# hv_mux_tr_sw.net
KiCad netlist of a schematic drawn in Altium Designer
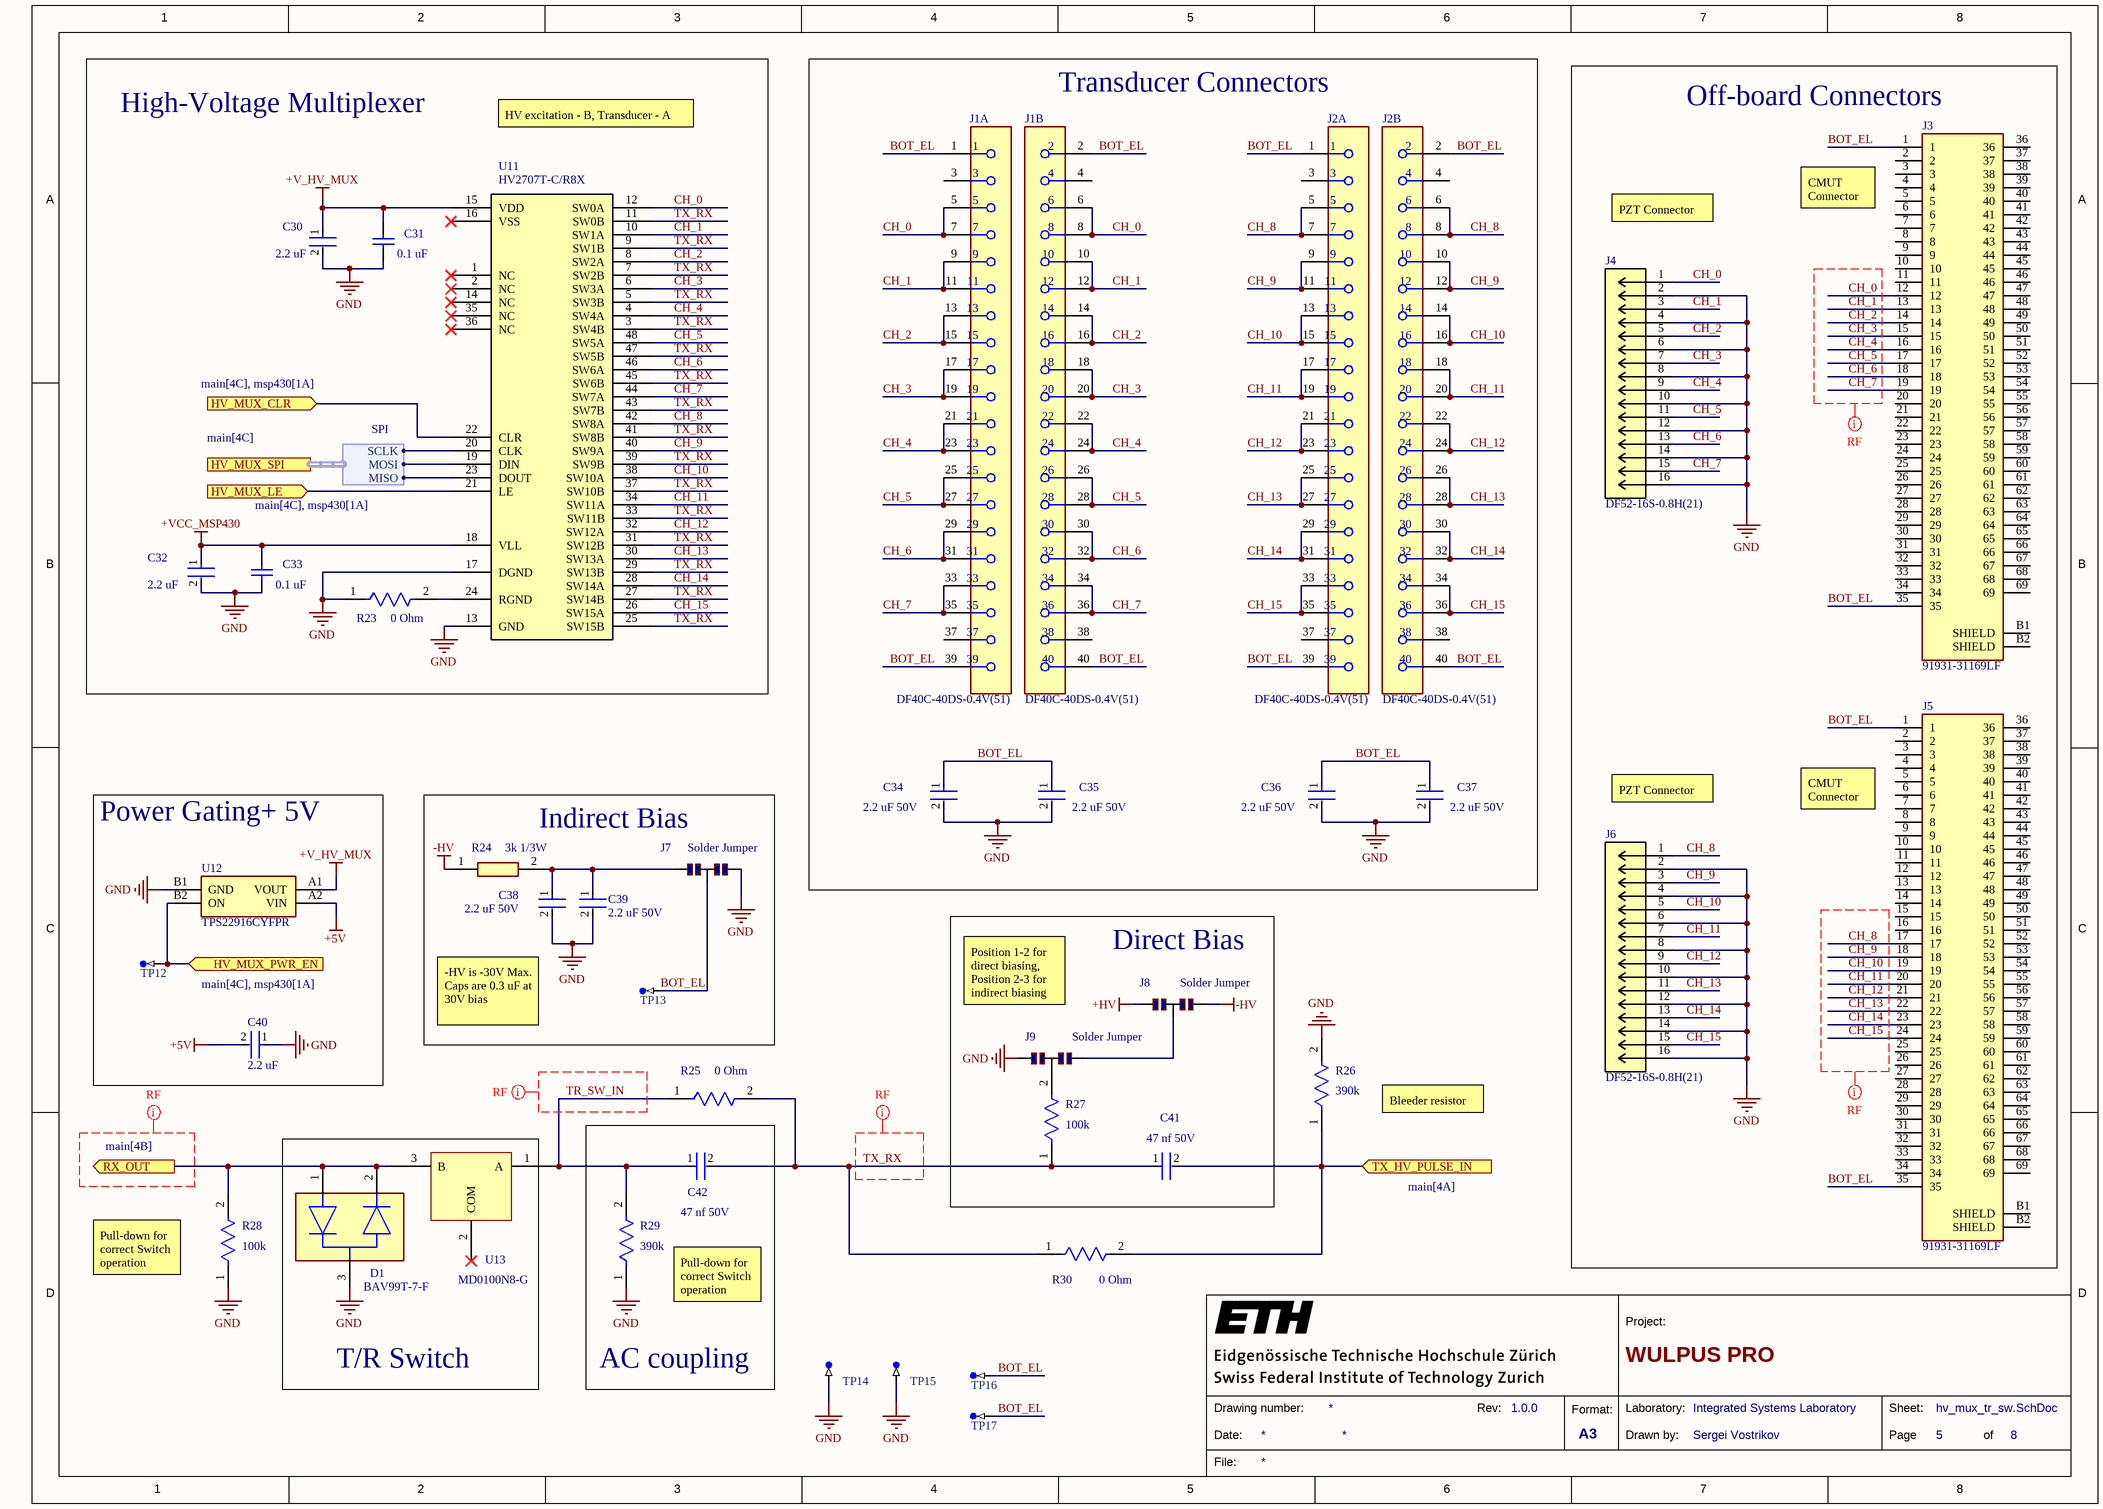
[diagram p0: hv_mux_tr_sw.SchDoc]

(export (version "E")
  (design (tool "Eeschema 10.0.6"))
  (components
    (comp (ref "C30")
      (value "2.2 uF")
      (footprint "FP-C1005-050-0_15-0_1-MFG")
      (description "C1005X7S1A225K050BC")
      (fields (field (name "TOLERANCE") "10%"))
      (libsource (lib "Altium Content Vault") (part "b4654b650e69147ec39a6b967a45e02"))
    )
    (comp (ref "C31")
      (value "0.1 uF")
      (footprint "CAPC1005X55X30LL05T10")
      (description "C0402C104K4RACTU")
      (fields (field (name "MANUFACTURER") "Kemet"))
      (libsource (lib "Altium Content Vault") (part "CAP"))
    )
    (comp (ref "C32")
      (value "2.2 uF")
      (footprint "FP-C1005-050-0_15-0_1-MFG")
      (description "C1005X7S1A225K050BC")
      (fields (field (name "TOLERANCE") "10%"))
      (libsource (lib "Altium Content Vault") (part "b4654b650e69147ec39a6b967a45e02"))
    )
    (comp (ref "C33")
      (value "0.1 uF")
      (footprint "CAPC1005X55X30LL05T10")
      (description "C0402C104K4RACTU")
      (fields (field (name "MANUFACTURER") "Kemet"))
      (libsource (lib "Altium Content Vault") (part "CAP"))
    )
    (comp (ref "C34")
      (value "2.2 uF 50V")
      (footprint "FP-GRM188-0_2-IPC_B")
      (description "GRM188R61H225ME11")
      (fields (field (name "TOLERANCE") "20%"))
      (libsource (lib "Altium Content Vault") (part "11868f565c42a9108669ba33697ecf6"))
    )
    (comp (ref "C35")
      (value "2.2 uF 50V")
      (footprint "FP-GRM188-0_2-IPC_B")
      (description "GRM188R61H225ME11")
      (fields (field (name "TOLERANCE") "20%"))
      (libsource (lib "Altium Content Vault") (part "11868f565c42a9108669ba33697ecf6"))
    )
    (comp (ref "C36")
      (value "2.2 uF 50V")
      (footprint "FP-GRM188-0_2-IPC_B")
      (description "GRM188R61H225ME11")
      (fields (field (name "TOLERANCE") "20%"))
      (libsource (lib "Altium Content Vault") (part "11868f565c42a9108669ba33697ecf6"))
    )
    (comp (ref "C37")
      (value "2.2 uF 50V")
      (footprint "FP-GRM188-0_2-IPC_B")
      (description "GRM188R61H225ME11")
      (fields (field (name "TOLERANCE") "20%"))
      (libsource (lib "Altium Content Vault") (part "11868f565c42a9108669ba33697ecf6"))
    )
    (comp (ref "C38")
      (value "2.2 uF 50V")
      (footprint "FP-GRM188-0_2-IPC_B")
      (description "GRM188R61H225ME11")
      (fields (field (name "TOLERANCE") "20%"))
      (libsource (lib "Altium Content Vault") (part "11868f565c42a9108669ba33697ecf6"))
    )
    (comp (ref "C39")
      (value "2.2 uF 50V")
      (footprint "FP-GRM188-0_2-IPC_B")
      (description "GRM188R61H225ME11")
      (fields (field (name "TOLERANCE") "20%"))
      (libsource (lib "Altium Content Vault") (part "11868f565c42a9108669ba33697ecf6"))
    )
    (comp (ref "C40")
      (value "2.2 uF")
      (footprint "FP-C1005-050-0_15-0_1-MFG")
      (description "C1005X7S1A225K050BC")
      (fields (field (name "TOLERANCE") "10%"))
      (libsource (lib "Altium Content Vault") (part "b4654b650e69147ec39a6b967a45e02"))
    )
    (comp (ref "C41")
      (value "47 nf 50V")
      (footprint "FP-GRM155-0_05-IPC_C")
      (description "GRM155R71H473ME14D")
      (fields (field (name "TOLERANCE") "20%"))
      (libsource (lib "Altium Content Vault") (part "02cd4be3c70576c341d710602a673aa"))
    )
    (comp (ref "C42")
      (value "47 nf 50V")
      (footprint "FP-GRM155-0_05-IPC_C")
      (description "GRM155R71H473ME14D")
      (fields (field (name "TOLERANCE") "20%"))
      (libsource (lib "Altium Content Vault") (part "02cd4be3c70576c341d710602a673aa"))
    )
    (comp (ref "D1")
      (value "BAV99T-7-F")
      (footprint "FP-SOT523-MFG")
      (description "DIODE ARRAY GP 85V 75MA SOT523")
      (fields
        (field (name "OCTOPART") "https://octopart.com/bav99t-7-f-diodes+inc.-326340")
        (field (name "MANUFACTURER") "Diodes Inc.")
      )
      (libsource (lib "Altium Content Vault") (part "070e4dda4d860bc04de3109e77921ad"))
    )
    (comp (ref "J1")
      (value "DF40C-40DS-0.4V(51)")
      (footprint "FP-DF40C-40DS-0_4V_51-MFG")
      (description "CONN RCPT 40POS SMD GOLD")
      (fields
        (field (name "MANUFACTURER") "Hirose")
        (field (name "OCTOPART") "https://octopart.com/df40c-40ds-0.4v%2851%29-hirose-19073526")
      )
      (libsource (lib "Altium Content Vault") (part "7acf1c4a8db21028d11741a46a6ec78"))
    )
    (comp (ref "J2")
      (value "DF40C-40DS-0.4V(51)")
      (footprint "FP-DF40C-40DS-0_4V_51-MFG")
      (description "CONN RCPT 40POS SMD GOLD")
      (fields
        (field (name "MANUFACTURER") "Hirose")
        (field (name "OCTOPART") "https://octopart.com/df40c-40ds-0.4v%2851%29-hirose-19073526")
      )
      (libsource (lib "Altium Content Vault") (part "7acf1c4a8db21028d11741a46a6ec78"))
    )
    (comp (ref "J3")
      (value "91931-31169LF")
      (footprint "cmut_conn:FRAMETOME_91931-31169LF")
      (description "Conn; Rect; Industrial; MezzanineRECP; 69Cnts; SMT; I-IndustrialSeries")
      (libsource (lib "cmut_conn") (part "91931-31169LF"))
    )
    (comp (ref "J4")
      (value "DF52-16S-0.8H(21)")
      (footprint "CONN_DF52-16S-0.8H(21)_HIR")
      (description "No Description Available")
      (fields (field (name "COPYRIGHT") "Copyright (C) 2022 Ultra Librarian. All rights reserved."))
      (libsource (lib "wulpus_hv") (part "DF52-16S-0.8H(21)"))
    )
    (comp (ref "J5")
      (value "91931-31169LF")
      (footprint "cmut_conn:FRAMETOME_91931-31169LF")
      (description "Conn; Rect; Industrial; MezzanineRECP; 69Cnts; SMT; I-IndustrialSeries")
      (libsource (lib "cmut_conn") (part "91931-31169LF"))
    )
    (comp (ref "J6")
      (value "DF52-16S-0.8H(21)")
      (footprint "CONN_DF52-16S-0.8H(21)_HIR")
      (description "No Description Available")
      (fields (field (name "COPYRIGHT") "Copyright (C) 2022 Ultra Librarian. All rights reserved."))
      (libsource (lib "wulpus_hv") (part "DF52-16S-0.8H(21)"))
    )
    (comp (ref "J7")
      (value "Solder Jumper")
      (footprint "Jumper 3 pins")
      (description "Solder Jumper 3 Pads")
      (libsource (lib "ETHZ Vault") (part "Solder Jumper 3-pads"))
    )
    (comp (ref "J8")
      (value "Solder Jumper")
      (footprint "Jumper 3 pins")
      (description "Solder Jumper 3 Pads")
      (libsource (lib "ETHZ Vault") (part "Solder Jumper 3-pads"))
    )
    (comp (ref "J9")
      (value "Solder Jumper")
      (footprint "Jumper 3 pins")
      (description "Solder Jumper 3 Pads")
      (libsource (lib "ETHZ Vault") (part "Solder Jumper 3-pads"))
    )
    (comp (ref "R23")
      (value "0 Ohm")
      (footprint "FP-CRCW0402-e3-IPC_C")
      (description "CRCW04020000Z0ED")
      (fields (field (name "TOLERANCE") "5%"))
      (libsource (lib "Altium Content Vault") (part "1029c3af85768c4190bb7ad29bc67b5"))
    )
    (comp (ref "R24")
      (value "3k 1/3W")
      (footprint "SamacSys:ERJP03_PA3_(0603)")
      (description "ERJ-PA3J302V")
      (fields (field (name "MOUSER PART NUMBER") "667-ERJ-PA3J302V"))
      (libsource (lib "*") (part "ERJ-PA3J302V"))
    )
    (comp (ref "R25")
      (value "0 Ohm")
      (footprint "FP-CRCW0402-e3-IPC_C")
      (description "CRCW04020000Z0ED")
      (fields (field (name "TOLERANCE") "5%"))
      (libsource (lib "Altium Content Vault") (part "1029c3af85768c4190bb7ad29bc67b5"))
    )
    (comp (ref "R26")
      (value "390k")
      (footprint "FP-RC1005-MFG")
      (description "RC1005F394CS")
      (fields (field (name "TOLERANCE") "1%"))
      (libsource (lib "Altium Content Vault") (part "1029c3af85768c4190bb7ad29bc67b5"))
    )
    (comp (ref "R27")
      (value "100k")
      (footprint "FP-ERJ2RK-IPC_C")
      (description "ERJ-2RKF1003X")
      (fields (field (name "TOLERANCE") "1%"))
      (libsource (lib "Altium Content Vault") (part "1029c3af85768c4190bb7ad29bc67b5"))
    )
    (comp (ref "R28")
      (value "100k")
      (footprint "FP-ERJ2RK-IPC_C")
      (description "ERJ-2RKF1003X")
      (fields (field (name "TOLERANCE") "1%"))
      (libsource (lib "Altium Content Vault") (part "1029c3af85768c4190bb7ad29bc67b5"))
    )
    (comp (ref "R29")
      (value "390k")
      (footprint "FP-RC1005-MFG")
      (description "RC1005F394CS")
      (fields (field (name "TOLERANCE") "1%"))
      (libsource (lib "Altium Content Vault") (part "1029c3af85768c4190bb7ad29bc67b5"))
    )
    (comp (ref "R30")
      (value "0 Ohm")
      (footprint "FP-CRCW0402-e3-IPC_C")
      (description "CRCW04020000Z0ED")
      (fields (field (name "TOLERANCE") "5%"))
      (libsource (lib "Altium Content Vault") (part "1029c3af85768c4190bb7ad29bc67b5"))
    )
    (comp (ref "TP12")
      (value "TP-SM-C-100")
      (footprint "TP-SM-C-100")
      (description "Test Point, Surface Mount, Circular, Pad Diameter 1 mm")
      (libsource (lib "wulpus") (part "CMP-0484-00002-1"))
    )
    (comp (ref "TP13")
      (value "TP-SM-C-100")
      (footprint "TP-SM-C-100")
      (description "Test Point, Surface Mount, Circular, Pad Diameter 1 mm")
      (libsource (lib "wulpus") (part "CMP-0484-00002-1"))
    )
    (comp (ref "TP14")
      (value "TP-SM-C-100")
      (footprint "TP-SM-C-100")
      (description "Test Point, Surface Mount, Circular, Pad Diameter 1 mm")
      (libsource (lib "wulpus") (part "CMP-0484-00002-1"))
    )
    (comp (ref "TP15")
      (value "TP-SM-C-100")
      (footprint "TP-SM-C-100")
      (description "Test Point, Surface Mount, Circular, Pad Diameter 1 mm")
      (libsource (lib "wulpus") (part "CMP-0484-00002-1"))
    )
    (comp (ref "TP16")
      (value "TP-SM-C-100")
      (footprint "TP-SM-C-100")
      (description "Test Point, Surface Mount, Circular, Pad Diameter 1 mm")
      (libsource (lib "wulpus") (part "CMP-0484-00002-1"))
    )
    (comp (ref "TP17")
      (value "TP-SM-C-100")
      (footprint "TP-SM-C-100")
      (description "Test Point, Surface Mount, Circular, Pad Diameter 1 mm")
      (libsource (lib "wulpus") (part "CMP-0484-00002-1"))
    )
    (comp (ref "U11")
      (value "HV2707T-C/R8X")
      (footprint "LQFP48_7X7MC_MCH")
      (description "16-CH 200V No Hv Bias Switch (SPST), 2 Bleed Resistor 48 LQFP 7X7X1.4MM T/r Rohs Compliant: Yes")
      (fields
        (field (name "MANUFACTURER") "Microchip")
        (field (name "MANUFACTURER PART NUMBER") "HV2707T-C/R8X")
      )
      (libsource (lib "wulpus_hv") (part "HV2707T-C/R8X"))
    )
    (comp (ref "U12")
      (value "TPS22916CYFPR")
      (footprint "BGA4C40P2X2_78X78X50")
      (description "TPS22916 5.5-V, 2-A Ultra-Low Leakage Load Switch")
      (libsource (lib "TPS22916CYFPR") (part "TPS22916CYFPR"))
    )
    (comp (ref "U13")
      (value "MD0100N8-G")
      (footprint "AMP_PHA-1+")
      (libsource (lib "MD01000") (part "MD0100"))
    )
  )
  (nets
    (net (code "2") (name "+5V") (class "Default")
      (node (ref "C40") (pin "2") (pinfunction "2_2") (pintype "passive"))
      (node (ref "U12") (pin "A2") (pinfunction "VIN_A2") (pintype "passive"))
    )
    (net (code "3") (name "+HV") (class "Default")
      (node (ref "J8") (pin "1") (pinfunction "1_1") (pintype "passive"))
    )
    (net (code "4") (name "+VCC_MSP430") (class "Default")
      (node (ref "C32") (pin "1") (pinfunction "1_1") (pintype "passive"))
      (node (ref "C33") (pin "2") (pinfunction "2_2") (pintype "passive"))
      (node (ref "U11") (pin "18") (pinfunction "VLL_18") (pintype "passive"))
    )
    (net (code "5") (name "+V_HV_MUX") (class "Default")
      (node (ref "C30") (pin "1") (pinfunction "1_1") (pintype "passive"))
      (node (ref "C31") (pin "2") (pinfunction "2_2") (pintype "passive"))
      (node (ref "U11") (pin "15") (pinfunction "VDD_15") (pintype "passive"))
      (node (ref "U12") (pin "A1") (pinfunction "VOUT_A1") (pintype "passive"))
    )
    (net (code "6") (name "-HV") (class "Default")
      (node (ref "J8") (pin "3") (pinfunction "3_3") (pintype "passive"))
      (node (ref "R24") (pin "1") (pinfunction "1_1") (pintype "passive"))
    )
    (net (code "7") (name "/BOT_EL") (class "Default")
      (node (ref "C34") (pin "1") (pinfunction "1_1") (pintype "passive"))
      (node (ref "C35") (pin "1") (pinfunction "1_1") (pintype "passive"))
      (node (ref "C36") (pin "1") (pinfunction "1_1") (pintype "passive"))
      (node (ref "C37") (pin "1") (pinfunction "1_1") (pintype "passive"))
      (node (ref "J1") (pin "1") (pinfunction "1_1") (pintype "passive"))
      (node (ref "J1") (pin "2") (pinfunction "2_2") (pintype "passive"))
      (node (ref "J1") (pin "39") (pinfunction "39_39") (pintype "passive"))
      (node (ref "J1") (pin "40") (pinfunction "40_40") (pintype "passive"))
      (node (ref "J2") (pin "1") (pinfunction "1_1") (pintype "passive"))
      (node (ref "J2") (pin "2") (pinfunction "2_2") (pintype "passive"))
      (node (ref "J2") (pin "39") (pinfunction "39_39") (pintype "passive"))
      (node (ref "J2") (pin "40") (pinfunction "40_40") (pintype "passive"))
      (node (ref "J3") (pin "1") (pinfunction "1_1") (pintype "passive"))
      (node (ref "J3") (pin "35") (pinfunction "35_35") (pintype "passive"))
      (node (ref "J5") (pin "1") (pinfunction "1_1") (pintype "passive"))
      (node (ref "J5") (pin "35") (pinfunction "35_35") (pintype "passive"))
      (node (ref "J7") (pin "2") (pinfunction "2_2") (pintype "passive"))
      (node (ref "TP13") (pin "1") (pinfunction "1_1") (pintype "input"))
      (node (ref "TP16") (pin "1") (pinfunction "1_1") (pintype "input"))
      (node (ref "TP17") (pin "1") (pinfunction "1_1") (pintype "input"))
    )
    (net (code "8") (name "/CH_0") (class "Default")
      (node (ref "J1") (pin "5") (pinfunction "5_5") (pintype "passive"))
      (node (ref "J1") (pin "6") (pinfunction "6_6") (pintype "passive"))
      (node (ref "J1") (pin "7") (pinfunction "7_7") (pintype "passive"))
      (node (ref "J1") (pin "8") (pinfunction "8_8") (pintype "passive"))
      (node (ref "J3") (pin "12") (pinfunction "12_12") (pintype "passive"))
      (node (ref "J4") (pin "1") (pinfunction "1_1") (pintype "passive"))
      (node (ref "U11") (pin "12") (pinfunction "SW0A_12") (pintype "passive"))
    )
    (net (code "9") (name "/CH_1") (class "Default")
      (node (ref "J1") (pin "10") (pinfunction "10_10") (pintype "passive"))
      (node (ref "J1") (pin "11") (pinfunction "11_11") (pintype "passive"))
      (node (ref "J1") (pin "12") (pinfunction "12_12") (pintype "passive"))
      (node (ref "J1") (pin "9") (pinfunction "9_9") (pintype "passive"))
      (node (ref "J3") (pin "13") (pinfunction "13_13") (pintype "passive"))
      (node (ref "J4") (pin "3") (pinfunction "3_3") (pintype "passive"))
      (node (ref "U11") (pin "10") (pinfunction "SW1A_10") (pintype "passive"))
    )
    (net (code "10") (name "/CH_2") (class "Default")
      (node (ref "J1") (pin "13") (pinfunction "13_13") (pintype "passive"))
      (node (ref "J1") (pin "14") (pinfunction "14_14") (pintype "passive"))
      (node (ref "J1") (pin "15") (pinfunction "15_15") (pintype "passive"))
      (node (ref "J1") (pin "16") (pinfunction "16_16") (pintype "passive"))
      (node (ref "J3") (pin "14") (pinfunction "14_14") (pintype "passive"))
      (node (ref "J4") (pin "5") (pinfunction "5_5") (pintype "passive"))
      (node (ref "U11") (pin "8") (pinfunction "SW2A_8") (pintype "passive"))
    )
    (net (code "11") (name "/CH_3") (class "Default")
      (node (ref "J1") (pin "17") (pinfunction "17_17") (pintype "passive"))
      (node (ref "J1") (pin "18") (pinfunction "18_18") (pintype "passive"))
      (node (ref "J1") (pin "19") (pinfunction "19_19") (pintype "passive"))
      (node (ref "J1") (pin "20") (pinfunction "20_20") (pintype "passive"))
      (node (ref "J3") (pin "15") (pinfunction "15_15") (pintype "passive"))
      (node (ref "J4") (pin "7") (pinfunction "7_7") (pintype "passive"))
      (node (ref "U11") (pin "6") (pinfunction "SW3A_6") (pintype "passive"))
    )
    (net (code "12") (name "/CH_4") (class "Default")
      (node (ref "J1") (pin "21") (pinfunction "21_21") (pintype "passive"))
      (node (ref "J1") (pin "22") (pinfunction "22_22") (pintype "passive"))
      (node (ref "J1") (pin "23") (pinfunction "23_23") (pintype "passive"))
      (node (ref "J1") (pin "24") (pinfunction "24_24") (pintype "passive"))
      (node (ref "J3") (pin "16") (pinfunction "16_16") (pintype "passive"))
      (node (ref "J4") (pin "9") (pinfunction "9_9") (pintype "passive"))
      (node (ref "U11") (pin "4") (pinfunction "SW4A_4") (pintype "passive"))
    )
    (net (code "13") (name "/CH_5") (class "Default")
      (node (ref "J1") (pin "25") (pinfunction "25_25") (pintype "passive"))
      (node (ref "J1") (pin "26") (pinfunction "26_26") (pintype "passive"))
      (node (ref "J1") (pin "27") (pinfunction "27_27") (pintype "passive"))
      (node (ref "J1") (pin "28") (pinfunction "28_28") (pintype "passive"))
      (node (ref "J3") (pin "17") (pinfunction "17_17") (pintype "passive"))
      (node (ref "J4") (pin "11") (pinfunction "11_11") (pintype "passive"))
      (node (ref "U11") (pin "48") (pinfunction "SW5A_48") (pintype "passive"))
    )
    (net (code "14") (name "/CH_6") (class "Default")
      (node (ref "J1") (pin "29") (pinfunction "29_29") (pintype "passive"))
      (node (ref "J1") (pin "30") (pinfunction "30_30") (pintype "passive"))
      (node (ref "J1") (pin "31") (pinfunction "31_31") (pintype "passive"))
      (node (ref "J1") (pin "32") (pinfunction "32_32") (pintype "passive"))
      (node (ref "J3") (pin "18") (pinfunction "18_18") (pintype "passive"))
      (node (ref "J4") (pin "13") (pinfunction "13_13") (pintype "passive"))
      (node (ref "U11") (pin "46") (pinfunction "SW6A_46") (pintype "passive"))
    )
    (net (code "15") (name "/CH_7") (class "Default")
      (node (ref "J1") (pin "33") (pinfunction "33_33") (pintype "passive"))
      (node (ref "J1") (pin "34") (pinfunction "34_34") (pintype "passive"))
      (node (ref "J1") (pin "35") (pinfunction "35_35") (pintype "passive"))
      (node (ref "J1") (pin "36") (pinfunction "36_36") (pintype "passive"))
      (node (ref "J3") (pin "19") (pinfunction "19_19") (pintype "passive"))
      (node (ref "J4") (pin "15") (pinfunction "15_15") (pintype "passive"))
      (node (ref "U11") (pin "44") (pinfunction "SW7A_44") (pintype "passive"))
    )
    (net (code "16") (name "/CH_8") (class "Default")
      (node (ref "J2") (pin "5") (pinfunction "5_5") (pintype "passive"))
      (node (ref "J2") (pin "6") (pinfunction "6_6") (pintype "passive"))
      (node (ref "J2") (pin "7") (pinfunction "7_7") (pintype "passive"))
      (node (ref "J2") (pin "8") (pinfunction "8_8") (pintype "passive"))
      (node (ref "J5") (pin "17") (pinfunction "17_17") (pintype "passive"))
      (node (ref "J6") (pin "1") (pinfunction "1_1") (pintype "passive"))
      (node (ref "U11") (pin "42") (pinfunction "SW8A_42") (pintype "passive"))
    )
    (net (code "17") (name "/CH_9") (class "Default")
      (node (ref "J2") (pin "10") (pinfunction "10_10") (pintype "passive"))
      (node (ref "J2") (pin "11") (pinfunction "11_11") (pintype "passive"))
      (node (ref "J2") (pin "12") (pinfunction "12_12") (pintype "passive"))
      (node (ref "J2") (pin "9") (pinfunction "9_9") (pintype "passive"))
      (node (ref "J5") (pin "18") (pinfunction "18_18") (pintype "passive"))
      (node (ref "J6") (pin "3") (pinfunction "3_3") (pintype "passive"))
      (node (ref "U11") (pin "40") (pinfunction "SW9A_40") (pintype "passive"))
    )
    (net (code "18") (name "/CH_10") (class "Default")
      (node (ref "J2") (pin "13") (pinfunction "13_13") (pintype "passive"))
      (node (ref "J2") (pin "14") (pinfunction "14_14") (pintype "passive"))
      (node (ref "J2") (pin "15") (pinfunction "15_15") (pintype "passive"))
      (node (ref "J2") (pin "16") (pinfunction "16_16") (pintype "passive"))
      (node (ref "J5") (pin "19") (pinfunction "19_19") (pintype "passive"))
      (node (ref "J6") (pin "5") (pinfunction "5_5") (pintype "passive"))
      (node (ref "U11") (pin "38") (pinfunction "SW10A_38") (pintype "passive"))
    )
    (net (code "19") (name "/CH_11") (class "Default")
      (node (ref "J2") (pin "17") (pinfunction "17_17") (pintype "passive"))
      (node (ref "J2") (pin "18") (pinfunction "18_18") (pintype "passive"))
      (node (ref "J2") (pin "19") (pinfunction "19_19") (pintype "passive"))
      (node (ref "J2") (pin "20") (pinfunction "20_20") (pintype "passive"))
      (node (ref "J5") (pin "20") (pinfunction "20_20") (pintype "passive"))
      (node (ref "J6") (pin "7") (pinfunction "7_7") (pintype "passive"))
      (node (ref "U11") (pin "34") (pinfunction "SW11A_34") (pintype "passive"))
    )
    (net (code "20") (name "/CH_12") (class "Default")
      (node (ref "J2") (pin "21") (pinfunction "21_21") (pintype "passive"))
      (node (ref "J2") (pin "22") (pinfunction "22_22") (pintype "passive"))
      (node (ref "J2") (pin "23") (pinfunction "23_23") (pintype "passive"))
      (node (ref "J2") (pin "24") (pinfunction "24_24") (pintype "passive"))
      (node (ref "J5") (pin "21") (pinfunction "21_21") (pintype "passive"))
      (node (ref "J6") (pin "9") (pinfunction "9_9") (pintype "passive"))
      (node (ref "U11") (pin "32") (pinfunction "SW12A_32") (pintype "passive"))
    )
    (net (code "21") (name "/CH_13") (class "Default")
      (node (ref "J2") (pin "25") (pinfunction "25_25") (pintype "passive"))
      (node (ref "J2") (pin "26") (pinfunction "26_26") (pintype "passive"))
      (node (ref "J2") (pin "27") (pinfunction "27_27") (pintype "passive"))
      (node (ref "J2") (pin "28") (pinfunction "28_28") (pintype "passive"))
      (node (ref "J5") (pin "22") (pinfunction "22_22") (pintype "passive"))
      (node (ref "J6") (pin "11") (pinfunction "11_11") (pintype "passive"))
      (node (ref "U11") (pin "30") (pinfunction "SW13A_30") (pintype "passive"))
    )
    (net (code "22") (name "/CH_14") (class "Default")
      (node (ref "J2") (pin "29") (pinfunction "29_29") (pintype "passive"))
      (node (ref "J2") (pin "30") (pinfunction "30_30") (pintype "passive"))
      (node (ref "J2") (pin "31") (pinfunction "31_31") (pintype "passive"))
      (node (ref "J2") (pin "32") (pinfunction "32_32") (pintype "passive"))
      (node (ref "J5") (pin "23") (pinfunction "23_23") (pintype "passive"))
      (node (ref "J6") (pin "13") (pinfunction "13_13") (pintype "passive"))
      (node (ref "U11") (pin "28") (pinfunction "SW14A_28") (pintype "passive"))
    )
    (net (code "23") (name "/CH_15") (class "Default")
      (node (ref "J2") (pin "33") (pinfunction "33_33") (pintype "passive"))
      (node (ref "J2") (pin "34") (pinfunction "34_34") (pintype "passive"))
      (node (ref "J2") (pin "35") (pinfunction "35_35") (pintype "passive"))
      (node (ref "J2") (pin "36") (pinfunction "36_36") (pintype "passive"))
      (node (ref "J5") (pin "24") (pinfunction "24_24") (pintype "passive"))
      (node (ref "J6") (pin "15") (pinfunction "15_15") (pintype "passive"))
      (node (ref "U11") (pin "26") (pinfunction "SW15A_26") (pintype "passive"))
    )
    (net (code "24") (name "/HV_MUX_CLR") (class "Default")
      (node (ref "U11") (pin "22") (pinfunction "CLR_22") (pintype "passive"))
    )
    (net (code "25") (name "/HV_MUX_LE") (class "Default")
      (node (ref "U11") (pin "21") (pinfunction "LE_21") (pintype "passive"))
    )
    (net (code "26") (name "/HV_MUX_PWR_EN") (class "Default")
      (node (ref "TP12") (pin "1") (pinfunction "1_1") (pintype "input"))
      (node (ref "U12") (pin "B2") (pinfunction "ON_B2") (pintype "passive"))
    )
    (net (code "27") (name "/MISO") (class "Default")
      (node (ref "U11") (pin "23") (pinfunction "DOUT_23") (pintype "passive"))
    )
    (net (code "28") (name "/MOSI") (class "Default")
      (node (ref "U11") (pin "19") (pinfunction "DIN_19") (pintype "passive"))
    )
    (net (code "29") (name "/RX_OUT") (class "Default")
      (node (ref "D1") (pin "1") (pinfunction "1_1") (pintype "passive"))
      (node (ref "D1") (pin "2") (pinfunction "2_2") (pintype "passive"))
      (node (ref "R28") (pin "2") (pinfunction "2_2") (pintype "passive"))
      (node (ref "U13") (pin "3") (pinfunction "B_3") (pintype "passive"))
    )
    (net (code "30") (name "/SCLK") (class "Default")
      (node (ref "U11") (pin "20") (pinfunction "CLK_20") (pintype "passive"))
    )
    (net (code "31") (name "/TR_SW_IN") (class "Default")
      (node (ref "C42") (pin "1") (pinfunction "1_1") (pintype "passive"))
      (node (ref "R25") (pin "1") (pinfunction "1_1") (pintype "passive"))
      (node (ref "R29") (pin "2") (pinfunction "2_2") (pintype "passive"))
      (node (ref "U13") (pin "1") (pinfunction "A_1") (pintype "passive"))
    )
    (net (code "32") (name "/TX_HV_PULSE_IN") (class "Default")
      (node (ref "C41") (pin "2") (pinfunction "2_2") (pintype "passive"))
      (node (ref "R26") (pin "1") (pinfunction "1_1") (pintype "passive"))
      (node (ref "R30") (pin "2") (pinfunction "2_2") (pintype "passive"))
    )
    (net (code "33") (name "/TX_RX") (class "Default")
      (node (ref "C41") (pin "1") (pinfunction "1_1") (pintype "passive"))
      (node (ref "C42") (pin "2") (pinfunction "2_2") (pintype "passive"))
      (node (ref "R25") (pin "2") (pinfunction "2_2") (pintype "passive"))
      (node (ref "R27") (pin "1") (pinfunction "1_1") (pintype "passive"))
      (node (ref "R30") (pin "1") (pinfunction "1_1") (pintype "passive"))
      (node (ref "U11") (pin "11") (pinfunction "SW0B_11") (pintype "passive"))
      (node (ref "U11") (pin "25") (pinfunction "SW15B_25") (pintype "passive"))
      (node (ref "U11") (pin "27") (pinfunction "SW14B_27") (pintype "passive"))
      (node (ref "U11") (pin "29") (pinfunction "SW13B_29") (pintype "passive"))
      (node (ref "U11") (pin "3") (pinfunction "SW4B_3") (pintype "passive"))
      (node (ref "U11") (pin "31") (pinfunction "SW12B_31") (pintype "passive"))
      (node (ref "U11") (pin "33") (pinfunction "SW11B_33") (pintype "passive"))
      (node (ref "U11") (pin "37") (pinfunction "SW10B_37") (pintype "passive"))
      (node (ref "U11") (pin "39") (pinfunction "SW9B_39") (pintype "passive"))
      (node (ref "U11") (pin "41") (pinfunction "SW8B_41") (pintype "passive"))
      (node (ref "U11") (pin "43") (pinfunction "SW7B_43") (pintype "passive"))
      (node (ref "U11") (pin "45") (pinfunction "SW6B_45") (pintype "passive"))
      (node (ref "U11") (pin "47") (pinfunction "SW5B_47") (pintype "passive"))
      (node (ref "U11") (pin "5") (pinfunction "SW3B_5") (pintype "passive"))
      (node (ref "U11") (pin "7") (pinfunction "SW2B_7") (pintype "passive"))
      (node (ref "U11") (pin "9") (pinfunction "SW1B_9") (pintype "passive"))
    )
    (net (code "35") (name "GND") (class "Default")
      (node (ref "C30") (pin "2") (pinfunction "2_2") (pintype "passive"))
      (node (ref "C31") (pin "1") (pinfunction "1_1") (pintype "passive"))
      (node (ref "C32") (pin "2") (pinfunction "2_2") (pintype "passive"))
      (node (ref "C33") (pin "1") (pinfunction "1_1") (pintype "passive"))
      (node (ref "C34") (pin "2") (pinfunction "2_2") (pintype "passive"))
      (node (ref "C35") (pin "2") (pinfunction "2_2") (pintype "passive"))
      (node (ref "C36") (pin "2") (pinfunction "2_2") (pintype "passive"))
      (node (ref "C37") (pin "2") (pinfunction "2_2") (pintype "passive"))
      (node (ref "C38") (pin "2") (pinfunction "2_2") (pintype "passive"))
      (node (ref "C39") (pin "2") (pinfunction "2_2") (pintype "passive"))
      (node (ref "C40") (pin "1") (pinfunction "1_1") (pintype "passive"))
      (node (ref "D1") (pin "3") (pinfunction "3_3") (pintype "passive"))
      (node (ref "J4") (pin "10") (pinfunction "10_10") (pintype "passive"))
      (node (ref "J4") (pin "12") (pinfunction "12_12") (pintype "passive"))
      (node (ref "J4") (pin "14") (pinfunction "14_14") (pintype "passive"))
      (node (ref "J4") (pin "16") (pinfunction "16_16") (pintype "passive"))
      (node (ref "J4") (pin "2") (pinfunction "2_2") (pintype "passive"))
      (node (ref "J4") (pin "4") (pinfunction "4_4") (pintype "passive"))
      (node (ref "J4") (pin "6") (pinfunction "6_6") (pintype "passive"))
      (node (ref "J4") (pin "8") (pinfunction "8_8") (pintype "passive"))
      (node (ref "J6") (pin "10") (pinfunction "10_10") (pintype "passive"))
      (node (ref "J6") (pin "12") (pinfunction "12_12") (pintype "passive"))
      (node (ref "J6") (pin "14") (pinfunction "14_14") (pintype "passive"))
      (node (ref "J6") (pin "16") (pinfunction "16_16") (pintype "passive"))
      (node (ref "J6") (pin "2") (pinfunction "2_2") (pintype "passive"))
      (node (ref "J6") (pin "4") (pinfunction "4_4") (pintype "passive"))
      (node (ref "J6") (pin "6") (pinfunction "6_6") (pintype "passive"))
      (node (ref "J6") (pin "8") (pinfunction "8_8") (pintype "passive"))
      (node (ref "J7") (pin "3") (pinfunction "3_3") (pintype "passive"))
      (node (ref "J9") (pin "1") (pinfunction "1_1") (pintype "passive"))
      (node (ref "R23") (pin "1") (pinfunction "1_1") (pintype "passive"))
      (node (ref "R26") (pin "2") (pinfunction "2_2") (pintype "passive"))
      (node (ref "R28") (pin "1") (pinfunction "1_1") (pintype "passive"))
      (node (ref "R29") (pin "1") (pinfunction "1_1") (pintype "passive"))
      (node (ref "TP14") (pin "1") (pinfunction "1_1") (pintype "input"))
      (node (ref "TP15") (pin "1") (pinfunction "1_1") (pintype "input"))
      (node (ref "U11") (pin "13") (pinfunction "GND_13") (pintype "passive"))
      (node (ref "U11") (pin "17") (pinfunction "DGND_17") (pintype "passive"))
      (node (ref "U12") (pin "B1") (pinfunction "GND_B1") (pintype "passive"))
    )
    (net (code "36") (name "Net-(C38-Pad1)") (class "Default")
      (node (ref "C38") (pin "1") (pinfunction "1_1") (pintype "passive"))
      (node (ref "C39") (pin "1") (pinfunction "1_1") (pintype "passive"))
      (node (ref "J7") (pin "1") (pinfunction "1_1") (pintype "passive"))
      (node (ref "R24") (pin "2") (pinfunction "2_2") (pintype "passive"))
    )
    (net (code "37") (name "Net-(J8-Pad2)") (class "Default")
      (node (ref "J8") (pin "2") (pinfunction "2_2") (pintype "passive"))
      (node (ref "J9") (pin "3") (pinfunction "3_3") (pintype "passive"))
    )
    (net (code "38") (name "Net-(J9-Pad2)") (class "Default")
      (node (ref "J9") (pin "2") (pinfunction "2_2") (pintype "passive"))
      (node (ref "R27") (pin "2") (pinfunction "2_2") (pintype "passive"))
    )
    (net (code "39") (name "Net-(U11-RGND)") (class "Default")
      (node (ref "R23") (pin "2") (pinfunction "2_2") (pintype "passive"))
      (node (ref "U11") (pin "24") (pinfunction "RGND_24") (pintype "passive"))
    )
    (net (code "40") (name "unconnected-(J1-Pad3)") (class "Default")
      (node (ref "J1") (pin "3") (pinfunction "3_3") (pintype "passive"))
    )
    (net (code "41") (name "unconnected-(J1-Pad4)") (class "Default")
      (node (ref "J1") (pin "4") (pinfunction "4_4") (pintype "passive"))
    )
    (net (code "42") (name "unconnected-(J1-Pad37)") (class "Default")
      (node (ref "J1") (pin "37") (pinfunction "37_37") (pintype "passive"))
    )
    (net (code "43") (name "unconnected-(J1-Pad38)") (class "Default")
      (node (ref "J1") (pin "38") (pinfunction "38_38") (pintype "passive"))
    )
    (net (code "44") (name "unconnected-(J2-Pad3)") (class "Default")
      (node (ref "J2") (pin "3") (pinfunction "3_3") (pintype "passive"))
    )
    (net (code "45") (name "unconnected-(J2-Pad4)") (class "Default")
      (node (ref "J2") (pin "4") (pinfunction "4_4") (pintype "passive"))
    )
    (net (code "46") (name "unconnected-(J2-Pad37)") (class "Default")
      (node (ref "J2") (pin "37") (pinfunction "37_37") (pintype "passive"))
    )
    (net (code "47") (name "unconnected-(J2-Pad38)") (class "Default")
      (node (ref "J2") (pin "38") (pinfunction "38_38") (pintype "passive"))
    )
    (net (code "48") (name "unconnected-(J3-Pad2)") (class "Default")
      (node (ref "J3") (pin "2") (pinfunction "2_2") (pintype "passive"))
    )
    (net (code "49") (name "unconnected-(J3-Pad3)") (class "Default")
      (node (ref "J3") (pin "3") (pinfunction "3_3") (pintype "passive"))
    )
    (net (code "50") (name "unconnected-(J3-Pad4)") (class "Default")
      (node (ref "J3") (pin "4") (pinfunction "4_4") (pintype "passive"))
    )
    (net (code "51") (name "unconnected-(J3-Pad5)") (class "Default")
      (node (ref "J3") (pin "5") (pinfunction "5_5") (pintype "passive"))
    )
    (net (code "52") (name "unconnected-(J3-Pad6)") (class "Default")
      (node (ref "J3") (pin "6") (pinfunction "6_6") (pintype "passive"))
    )
    (net (code "53") (name "unconnected-(J3-Pad7)") (class "Default")
      (node (ref "J3") (pin "7") (pinfunction "7_7") (pintype "passive"))
    )
    (net (code "54") (name "unconnected-(J3-Pad8)") (class "Default")
      (node (ref "J3") (pin "8") (pinfunction "8_8") (pintype "passive"))
    )
    (net (code "55") (name "unconnected-(J3-Pad9)") (class "Default")
      (node (ref "J3") (pin "9") (pinfunction "9_9") (pintype "passive"))
    )
    (net (code "56") (name "unconnected-(J3-Pad10)") (class "Default")
      (node (ref "J3") (pin "10") (pinfunction "10_10") (pintype "passive"))
    )
    (net (code "57") (name "unconnected-(J3-Pad11)") (class "Default")
      (node (ref "J3") (pin "11") (pinfunction "11_11") (pintype "passive"))
    )
    (net (code "58") (name "unconnected-(J3-Pad20)") (class "Default")
      (node (ref "J3") (pin "20") (pinfunction "20_20") (pintype "passive"))
    )
    (net (code "59") (name "unconnected-(J3-Pad21)") (class "Default")
      (node (ref "J3") (pin "21") (pinfunction "21_21") (pintype "passive"))
    )
    (net (code "60") (name "unconnected-(J3-Pad22)") (class "Default")
      (node (ref "J3") (pin "22") (pinfunction "22_22") (pintype "passive"))
    )
    (net (code "61") (name "unconnected-(J3-Pad23)") (class "Default")
      (node (ref "J3") (pin "23") (pinfunction "23_23") (pintype "passive"))
    )
    (net (code "62") (name "unconnected-(J3-Pad24)") (class "Default")
      (node (ref "J3") (pin "24") (pinfunction "24_24") (pintype "passive"))
    )
    (net (code "63") (name "unconnected-(J3-Pad25)") (class "Default")
      (node (ref "J3") (pin "25") (pinfunction "25_25") (pintype "passive"))
    )
    (net (code "64") (name "unconnected-(J3-Pad26)") (class "Default")
      (node (ref "J3") (pin "26") (pinfunction "26_26") (pintype "passive"))
    )
    (net (code "65") (name "unconnected-(J3-Pad27)") (class "Default")
      (node (ref "J3") (pin "27") (pinfunction "27_27") (pintype "passive"))
    )
    (net (code "66") (name "unconnected-(J3-Pad28)") (class "Default")
      (node (ref "J3") (pin "28") (pinfunction "28_28") (pintype "passive"))
    )
    (net (code "67") (name "unconnected-(J3-Pad29)") (class "Default")
      (node (ref "J3") (pin "29") (pinfunction "29_29") (pintype "passive"))
    )
    (net (code "68") (name "unconnected-(J3-Pad30)") (class "Default")
      (node (ref "J3") (pin "30") (pinfunction "30_30") (pintype "passive"))
    )
    (net (code "69") (name "unconnected-(J3-Pad31)") (class "Default")
      (node (ref "J3") (pin "31") (pinfunction "31_31") (pintype "passive"))
    )
    (net (code "70") (name "unconnected-(J3-Pad32)") (class "Default")
      (node (ref "J3") (pin "32") (pinfunction "32_32") (pintype "passive"))
    )
    (net (code "71") (name "unconnected-(J3-Pad33)") (class "Default")
      (node (ref "J3") (pin "33") (pinfunction "33_33") (pintype "passive"))
    )
    (net (code "72") (name "unconnected-(J3-Pad34)") (class "Default")
      (node (ref "J3") (pin "34") (pinfunction "34_34") (pintype "passive"))
    )
    (net (code "73") (name "unconnected-(J3-Pad36)") (class "Default")
      (node (ref "J3") (pin "36") (pinfunction "36_36") (pintype "passive"))
    )
    (net (code "74") (name "unconnected-(J3-Pad37)") (class "Default")
      (node (ref "J3") (pin "37") (pinfunction "37_37") (pintype "passive"))
    )
    (net (code "75") (name "unconnected-(J3-Pad38)") (class "Default")
      (node (ref "J3") (pin "38") (pinfunction "38_38") (pintype "passive"))
    )
    (net (code "76") (name "unconnected-(J3-Pad39)") (class "Default")
      (node (ref "J3") (pin "39") (pinfunction "39_39") (pintype "passive"))
    )
    (net (code "77") (name "unconnected-(J3-Pad40)") (class "Default")
      (node (ref "J3") (pin "40") (pinfunction "40_40") (pintype "passive"))
    )
    (net (code "78") (name "unconnected-(J3-Pad41)") (class "Default")
      (node (ref "J3") (pin "41") (pinfunction "41_41") (pintype "passive"))
    )
    (net (code "79") (name "unconnected-(J3-Pad42)") (class "Default")
      (node (ref "J3") (pin "42") (pinfunction "42_42") (pintype "passive"))
    )
    (net (code "80") (name "unconnected-(J3-Pad43)") (class "Default")
      (node (ref "J3") (pin "43") (pinfunction "43_43") (pintype "passive"))
    )
    (net (code "81") (name "unconnected-(J3-Pad44)") (class "Default")
      (node (ref "J3") (pin "44") (pinfunction "44_44") (pintype "passive"))
    )
    (net (code "82") (name "unconnected-(J3-Pad45)") (class "Default")
      (node (ref "J3") (pin "45") (pinfunction "45_45") (pintype "passive"))
    )
    (net (code "83") (name "unconnected-(J3-Pad46)") (class "Default")
      (node (ref "J3") (pin "46") (pinfunction "46_46") (pintype "passive"))
    )
    (net (code "84") (name "unconnected-(J3-Pad47)") (class "Default")
      (node (ref "J3") (pin "47") (pinfunction "47_47") (pintype "passive"))
    )
    (net (code "85") (name "unconnected-(J3-Pad48)") (class "Default")
      (node (ref "J3") (pin "48") (pinfunction "48_48") (pintype "passive"))
    )
    (net (code "86") (name "unconnected-(J3-Pad49)") (class "Default")
      (node (ref "J3") (pin "49") (pinfunction "49_49") (pintype "passive"))
    )
    (net (code "87") (name "unconnected-(J3-Pad50)") (class "Default")
      (node (ref "J3") (pin "50") (pinfunction "50_50") (pintype "passive"))
    )
    (net (code "88") (name "unconnected-(J3-Pad51)") (class "Default")
      (node (ref "J3") (pin "51") (pinfunction "51_51") (pintype "passive"))
    )
    (net (code "89") (name "unconnected-(J3-Pad52)") (class "Default")
      (node (ref "J3") (pin "52") (pinfunction "52_52") (pintype "passive"))
    )
    (net (code "90") (name "unconnected-(J3-Pad53)") (class "Default")
      (node (ref "J3") (pin "53") (pinfunction "53_53") (pintype "passive"))
    )
    (net (code "91") (name "unconnected-(J3-Pad54)") (class "Default")
      (node (ref "J3") (pin "54") (pinfunction "54_54") (pintype "passive"))
    )
    (net (code "92") (name "unconnected-(J3-Pad55)") (class "Default")
      (node (ref "J3") (pin "55") (pinfunction "55_55") (pintype "passive"))
    )
    (net (code "93") (name "unconnected-(J3-Pad56)") (class "Default")
      (node (ref "J3") (pin "56") (pinfunction "56_56") (pintype "passive"))
    )
    (net (code "94") (name "unconnected-(J3-Pad57)") (class "Default")
      (node (ref "J3") (pin "57") (pinfunction "57_57") (pintype "passive"))
    )
    (net (code "95") (name "unconnected-(J3-Pad58)") (class "Default")
      (node (ref "J3") (pin "58") (pinfunction "58_58") (pintype "passive"))
    )
    (net (code "96") (name "unconnected-(J3-Pad59)") (class "Default")
      (node (ref "J3") (pin "59") (pinfunction "59_59") (pintype "passive"))
    )
    (net (code "97") (name "unconnected-(J3-Pad60)") (class "Default")
      (node (ref "J3") (pin "60") (pinfunction "60_60") (pintype "passive"))
    )
    (net (code "98") (name "unconnected-(J3-Pad61)") (class "Default")
      (node (ref "J3") (pin "61") (pinfunction "61_61") (pintype "passive"))
    )
    (net (code "99") (name "unconnected-(J3-Pad62)") (class "Default")
      (node (ref "J3") (pin "62") (pinfunction "62_62") (pintype "passive"))
    )
    (net (code "100") (name "unconnected-(J3-Pad63)") (class "Default")
      (node (ref "J3") (pin "63") (pinfunction "63_63") (pintype "passive"))
    )
    (net (code "101") (name "unconnected-(J3-Pad64)") (class "Default")
      (node (ref "J3") (pin "64") (pinfunction "64_64") (pintype "passive"))
    )
    (net (code "102") (name "unconnected-(J3-Pad65)") (class "Default")
      (node (ref "J3") (pin "65") (pinfunction "65_65") (pintype "passive"))
    )
    (net (code "103") (name "unconnected-(J3-Pad66)") (class "Default")
      (node (ref "J3") (pin "66") (pinfunction "66_66") (pintype "passive"))
    )
    (net (code "104") (name "unconnected-(J3-Pad67)") (class "Default")
      (node (ref "J3") (pin "67") (pinfunction "67_67") (pintype "passive"))
    )
    (net (code "105") (name "unconnected-(J3-Pad68)") (class "Default")
      (node (ref "J3") (pin "68") (pinfunction "68_68") (pintype "passive"))
    )
    (net (code "106") (name "unconnected-(J3-Pad69)") (class "Default")
      (node (ref "J3") (pin "69") (pinfunction "69_69") (pintype "passive"))
    )
    (net (code "107") (name "unconnected-(J3-SHIELD-PadB1)") (class "Default")
      (node (ref "J3") (pin "B1") (pinfunction "SHIELD_B1") (pintype "passive"))
    )
    (net (code "108") (name "unconnected-(J3-SHIELD-PadB2)") (class "Default")
      (node (ref "J3") (pin "B2") (pinfunction "SHIELD_B2") (pintype "passive"))
    )
    (net (code "109") (name "unconnected-(J5-Pad2)") (class "Default")
      (node (ref "J5") (pin "2") (pinfunction "2_2") (pintype "passive"))
    )
    (net (code "110") (name "unconnected-(J5-Pad3)") (class "Default")
      (node (ref "J5") (pin "3") (pinfunction "3_3") (pintype "passive"))
    )
    (net (code "111") (name "unconnected-(J5-Pad4)") (class "Default")
      (node (ref "J5") (pin "4") (pinfunction "4_4") (pintype "passive"))
    )
    (net (code "112") (name "unconnected-(J5-Pad5)") (class "Default")
      (node (ref "J5") (pin "5") (pinfunction "5_5") (pintype "passive"))
    )
    (net (code "113") (name "unconnected-(J5-Pad6)") (class "Default")
      (node (ref "J5") (pin "6") (pinfunction "6_6") (pintype "passive"))
    )
    (net (code "114") (name "unconnected-(J5-Pad7)") (class "Default")
      (node (ref "J5") (pin "7") (pinfunction "7_7") (pintype "passive"))
    )
    (net (code "115") (name "unconnected-(J5-Pad8)") (class "Default")
      (node (ref "J5") (pin "8") (pinfunction "8_8") (pintype "passive"))
    )
    (net (code "116") (name "unconnected-(J5-Pad9)") (class "Default")
      (node (ref "J5") (pin "9") (pinfunction "9_9") (pintype "passive"))
    )
    (net (code "117") (name "unconnected-(J5-Pad10)") (class "Default")
      (node (ref "J5") (pin "10") (pinfunction "10_10") (pintype "passive"))
    )
    (net (code "118") (name "unconnected-(J5-Pad11)") (class "Default")
      (node (ref "J5") (pin "11") (pinfunction "11_11") (pintype "passive"))
    )
    (net (code "119") (name "unconnected-(J5-Pad12)") (class "Default")
      (node (ref "J5") (pin "12") (pinfunction "12_12") (pintype "passive"))
    )
    (net (code "120") (name "unconnected-(J5-Pad13)") (class "Default")
      (node (ref "J5") (pin "13") (pinfunction "13_13") (pintype "passive"))
    )
    (net (code "121") (name "unconnected-(J5-Pad14)") (class "Default")
      (node (ref "J5") (pin "14") (pinfunction "14_14") (pintype "passive"))
    )
    (net (code "122") (name "unconnected-(J5-Pad15)") (class "Default")
      (node (ref "J5") (pin "15") (pinfunction "15_15") (pintype "passive"))
    )
    (net (code "123") (name "unconnected-(J5-Pad16)") (class "Default")
      (node (ref "J5") (pin "16") (pinfunction "16_16") (pintype "passive"))
    )
    (net (code "124") (name "unconnected-(J5-Pad25)") (class "Default")
      (node (ref "J5") (pin "25") (pinfunction "25_25") (pintype "passive"))
    )
    (net (code "125") (name "unconnected-(J5-Pad26)") (class "Default")
      (node (ref "J5") (pin "26") (pinfunction "26_26") (pintype "passive"))
    )
    (net (code "126") (name "unconnected-(J5-Pad27)") (class "Default")
      (node (ref "J5") (pin "27") (pinfunction "27_27") (pintype "passive"))
    )
    (net (code "127") (name "unconnected-(J5-Pad28)") (class "Default")
      (node (ref "J5") (pin "28") (pinfunction "28_28") (pintype "passive"))
    )
    (net (code "128") (name "unconnected-(J5-Pad29)") (class "Default")
      (node (ref "J5") (pin "29") (pinfunction "29_29") (pintype "passive"))
    )
    (net (code "129") (name "unconnected-(J5-Pad30)") (class "Default")
      (node (ref "J5") (pin "30") (pinfunction "30_30") (pintype "passive"))
    )
    (net (code "130") (name "unconnected-(J5-Pad31)") (class "Default")
      (node (ref "J5") (pin "31") (pinfunction "31_31") (pintype "passive"))
    )
    (net (code "131") (name "unconnected-(J5-Pad32)") (class "Default")
      (node (ref "J5") (pin "32") (pinfunction "32_32") (pintype "passive"))
    )
    (net (code "132") (name "unconnected-(J5-Pad33)") (class "Default")
      (node (ref "J5") (pin "33") (pinfunction "33_33") (pintype "passive"))
    )
    (net (code "133") (name "unconnected-(J5-Pad34)") (class "Default")
      (node (ref "J5") (pin "34") (pinfunction "34_34") (pintype "passive"))
    )
    (net (code "134") (name "unconnected-(J5-Pad36)") (class "Default")
      (node (ref "J5") (pin "36") (pinfunction "36_36") (pintype "passive"))
    )
    (net (code "135") (name "unconnected-(J5-Pad37)") (class "Default")
      (node (ref "J5") (pin "37") (pinfunction "37_37") (pintype "passive"))
    )
    (net (code "136") (name "unconnected-(J5-Pad38)") (class "Default")
      (node (ref "J5") (pin "38") (pinfunction "38_38") (pintype "passive"))
    )
    (net (code "137") (name "unconnected-(J5-Pad39)") (class "Default")
      (node (ref "J5") (pin "39") (pinfunction "39_39") (pintype "passive"))
    )
    (net (code "138") (name "unconnected-(J5-Pad40)") (class "Default")
      (node (ref "J5") (pin "40") (pinfunction "40_40") (pintype "passive"))
    )
    (net (code "139") (name "unconnected-(J5-Pad41)") (class "Default")
      (node (ref "J5") (pin "41") (pinfunction "41_41") (pintype "passive"))
    )
    (net (code "140") (name "unconnected-(J5-Pad42)") (class "Default")
      (node (ref "J5") (pin "42") (pinfunction "42_42") (pintype "passive"))
    )
    (net (code "141") (name "unconnected-(J5-Pad43)") (class "Default")
      (node (ref "J5") (pin "43") (pinfunction "43_43") (pintype "passive"))
    )
    (net (code "142") (name "unconnected-(J5-Pad44)") (class "Default")
      (node (ref "J5") (pin "44") (pinfunction "44_44") (pintype "passive"))
    )
    (net (code "143") (name "unconnected-(J5-Pad45)") (class "Default")
      (node (ref "J5") (pin "45") (pinfunction "45_45") (pintype "passive"))
    )
    (net (code "144") (name "unconnected-(J5-Pad46)") (class "Default")
      (node (ref "J5") (pin "46") (pinfunction "46_46") (pintype "passive"))
    )
    (net (code "145") (name "unconnected-(J5-Pad47)") (class "Default")
      (node (ref "J5") (pin "47") (pinfunction "47_47") (pintype "passive"))
    )
    (net (code "146") (name "unconnected-(J5-Pad48)") (class "Default")
      (node (ref "J5") (pin "48") (pinfunction "48_48") (pintype "passive"))
    )
    (net (code "147") (name "unconnected-(J5-Pad49)") (class "Default")
      (node (ref "J5") (pin "49") (pinfunction "49_49") (pintype "passive"))
    )
    (net (code "148") (name "unconnected-(J5-Pad50)") (class "Default")
      (node (ref "J5") (pin "50") (pinfunction "50_50") (pintype "passive"))
    )
    (net (code "149") (name "unconnected-(J5-Pad51)") (class "Default")
      (node (ref "J5") (pin "51") (pinfunction "51_51") (pintype "passive"))
    )
    (net (code "150") (name "unconnected-(J5-Pad52)") (class "Default")
      (node (ref "J5") (pin "52") (pinfunction "52_52") (pintype "passive"))
    )
    (net (code "151") (name "unconnected-(J5-Pad53)") (class "Default")
      (node (ref "J5") (pin "53") (pinfunction "53_53") (pintype "passive"))
    )
    (net (code "152") (name "unconnected-(J5-Pad54)") (class "Default")
      (node (ref "J5") (pin "54") (pinfunction "54_54") (pintype "passive"))
    )
    (net (code "153") (name "unconnected-(J5-Pad55)") (class "Default")
      (node (ref "J5") (pin "55") (pinfunction "55_55") (pintype "passive"))
    )
    (net (code "154") (name "unconnected-(J5-Pad56)") (class "Default")
      (node (ref "J5") (pin "56") (pinfunction "56_56") (pintype "passive"))
    )
    (net (code "155") (name "unconnected-(J5-Pad57)") (class "Default")
      (node (ref "J5") (pin "57") (pinfunction "57_57") (pintype "passive"))
    )
    (net (code "156") (name "unconnected-(J5-Pad58)") (class "Default")
      (node (ref "J5") (pin "58") (pinfunction "58_58") (pintype "passive"))
    )
    (net (code "157") (name "unconnected-(J5-Pad59)") (class "Default")
      (node (ref "J5") (pin "59") (pinfunction "59_59") (pintype "passive"))
    )
    (net (code "158") (name "unconnected-(J5-Pad60)") (class "Default")
      (node (ref "J5") (pin "60") (pinfunction "60_60") (pintype "passive"))
    )
    (net (code "159") (name "unconnected-(J5-Pad61)") (class "Default")
      (node (ref "J5") (pin "61") (pinfunction "61_61") (pintype "passive"))
    )
    (net (code "160") (name "unconnected-(J5-Pad62)") (class "Default")
      (node (ref "J5") (pin "62") (pinfunction "62_62") (pintype "passive"))
    )
    (net (code "161") (name "unconnected-(J5-Pad63)") (class "Default")
      (node (ref "J5") (pin "63") (pinfunction "63_63") (pintype "passive"))
    )
    (net (code "162") (name "unconnected-(J5-Pad64)") (class "Default")
      (node (ref "J5") (pin "64") (pinfunction "64_64") (pintype "passive"))
    )
    (net (code "163") (name "unconnected-(J5-Pad65)") (class "Default")
      (node (ref "J5") (pin "65") (pinfunction "65_65") (pintype "passive"))
    )
    (net (code "164") (name "unconnected-(J5-Pad66)") (class "Default")
      (node (ref "J5") (pin "66") (pinfunction "66_66") (pintype "passive"))
    )
    (net (code "165") (name "unconnected-(J5-Pad67)") (class "Default")
      (node (ref "J5") (pin "67") (pinfunction "67_67") (pintype "passive"))
    )
    (net (code "166") (name "unconnected-(J5-Pad68)") (class "Default")
      (node (ref "J5") (pin "68") (pinfunction "68_68") (pintype "passive"))
    )
    (net (code "167") (name "unconnected-(J5-Pad69)") (class "Default")
      (node (ref "J5") (pin "69") (pinfunction "69_69") (pintype "passive"))
    )
    (net (code "168") (name "unconnected-(J5-SHIELD-PadB1)") (class "Default")
      (node (ref "J5") (pin "B1") (pinfunction "SHIELD_B1") (pintype "passive"))
    )
    (net (code "169") (name "unconnected-(J5-SHIELD-PadB2)") (class "Default")
      (node (ref "J5") (pin "B2") (pinfunction "SHIELD_B2") (pintype "passive"))
    )
    (net (code "170") (name "unconnected-(U11-NC-Pad1)") (class "Default")
      (node (ref "U11") (pin "1") (pinfunction "NC_1") (pintype "passive+no_connect"))
    )
    (net (code "171") (name "unconnected-(U11-NC-Pad2)") (class "Default")
      (node (ref "U11") (pin "2") (pinfunction "NC_2") (pintype "passive+no_connect"))
    )
    (net (code "172") (name "unconnected-(U11-NC-Pad14)") (class "Default")
      (node (ref "U11") (pin "14") (pinfunction "NC_14") (pintype "passive+no_connect"))
    )
    (net (code "173") (name "unconnected-(U11-NC-Pad35)") (class "Default")
      (node (ref "U11") (pin "35") (pinfunction "NC_35") (pintype "passive+no_connect"))
    )
    (net (code "174") (name "unconnected-(U11-NC-Pad36)") (class "Default")
      (node (ref "U11") (pin "36") (pinfunction "NC_36") (pintype "passive+no_connect"))
    )
    (net (code "175") (name "unconnected-(U11-VSS-Pad16)") (class "Default")
      (node (ref "U11") (pin "16") (pinfunction "VSS_16") (pintype "passive+no_connect"))
    )
    (net (code "176") (name "unconnected-(U13-COM-Pad2)") (class "Default")
      (node (ref "U13") (pin "2") (pinfunction "COM_2") (pintype "passive+no_connect"))
    )
  )
)
